# MotorController.net
KiCad netlist of a schematic drawn in Altium Designer
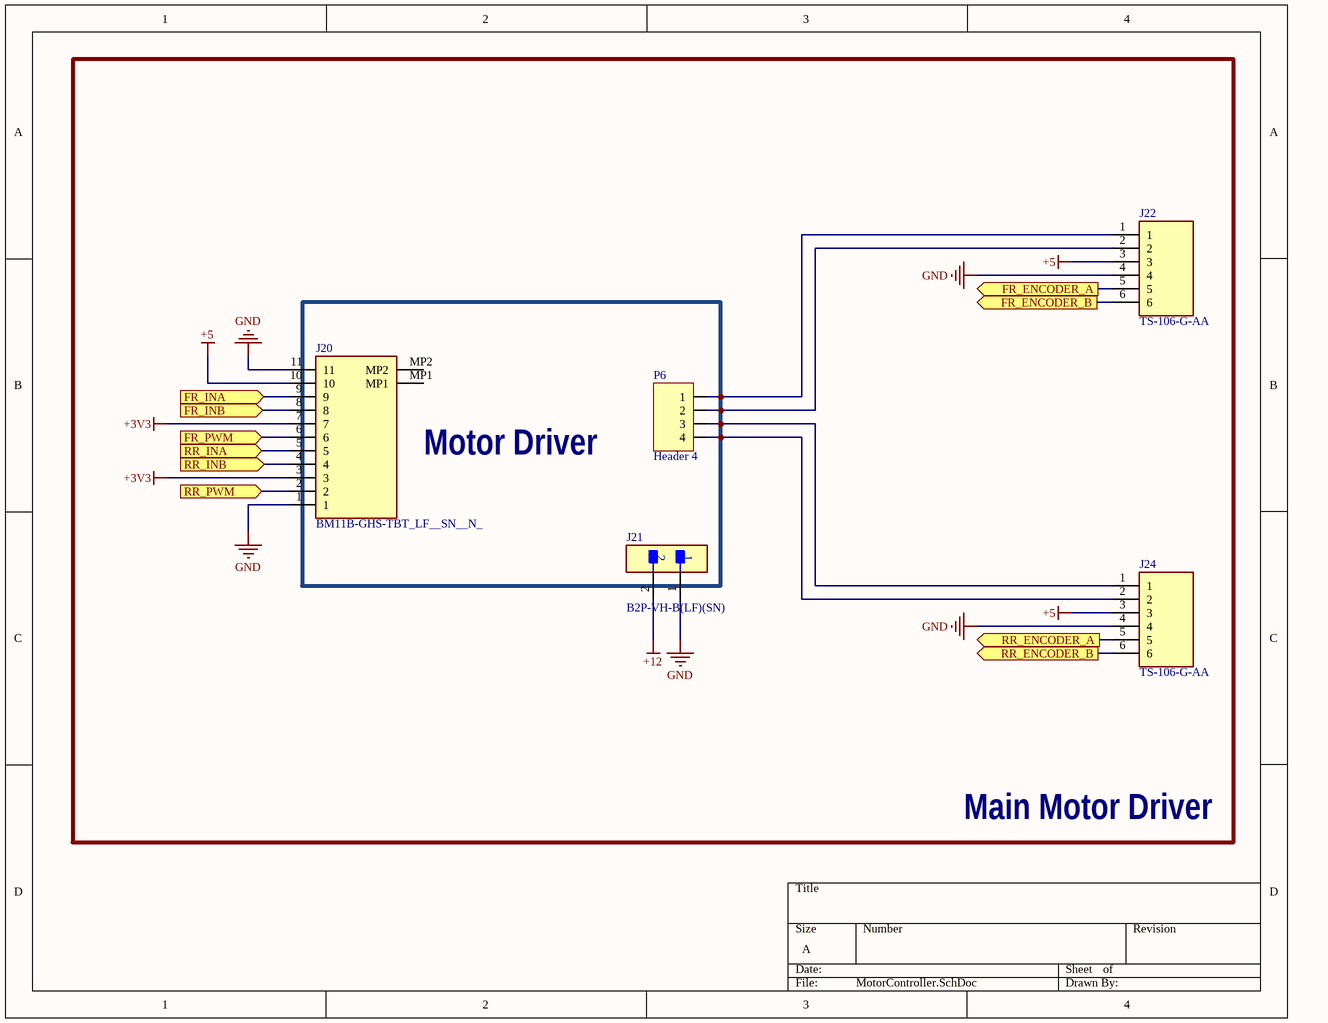
[diagram p0: MotorController.SchDoc]

(export (version "E")
  (design (tool "Eeschema 10.0.6"))
  (components
    (comp (ref "J20")
      (value "BM11B-GHS-TBT_LF__SN__N_")
      (footprint "SamacSys:BM11BGHSTBTLFSNN")
      (description "Connector")
      (fields (field (name "MANUFACTURER_PART_NUMBER") "BM11B-GHS-TBT(LF)(SN)(N)"))
      (libsource (lib "SamacSys") (part "BM11B-GHS-TBT_LF__SN__N_"))
    )
    (comp (ref "J21")
      (value "B2P-VH-B(LF)(SN)")
      (footprint "FP-B2P-VH-B_LF_SN-MFG")
      (description "CONN HEADER VERT 2POS 3.96MM")
      (libsource (lib "Altium Content Vault") (part "3bc925449376181038e59eaffc5286c"))
    )
    (comp (ref "J22")
      (value "TS-106-G-AA")
      (footprint "SamacSys:HDRV6W46P0X254_1X6_1524X254X676P")
      (description "Connector")
      (fields (field (name "MOUSER PART NUMBER") "200-TS106GAA"))
      (libsource (lib "SamacSys") (part "TS-106-G-AA"))
    )
    (comp (ref "J24")
      (value "TS-106-G-AA")
      (footprint "SamacSys:HDRV6W46P0X254_1X6_1524X254X676P")
      (description "Connector")
      (fields (field (name "MOUSER PART NUMBER") "200-TS106GAA"))
      (libsource (lib "SamacSys") (part "TS-106-G-AA"))
    )
    (comp (ref "P6")
      (value "Header 4")
      (footprint "HDR1X4")
      (description "Header, 4-Pin")
      (fields (field (name "PUBLISHER") "Altium Limited"))
      (libsource (lib "Miscellaneous Connectors") (part "Header 4"))
    )
  )
  (nets
    (net (code "1") (name "+3V3") (class "Default")
      (node (ref "J20") (pin "3") (pinfunction "3_3") (pintype "passive"))
      (node (ref "J20") (pin "7") (pinfunction "7_7") (pintype "passive"))
    )
    (net (code "2") (name "+5") (class "Default")
      (node (ref "J20") (pin "10") (pinfunction "10_10") (pintype "passive"))
      (node (ref "J22") (pin "3") (pinfunction "3_3") (pintype "passive"))
      (node (ref "J24") (pin "3") (pinfunction "3_3") (pintype "passive"))
    )
    (net (code "3") (name "+12") (class "Default")
      (node (ref "J21") (pin "2") (pinfunction "2_2") (pintype "passive"))
    )
    (net (code "4") (name "/FR_ENCODER_A") (class "Default")
      (node (ref "J22") (pin "5") (pinfunction "5_5") (pintype "passive"))
    )
    (net (code "5") (name "/FR_ENCODER_B") (class "Default")
      (node (ref "J22") (pin "6") (pinfunction "6_6") (pintype "passive"))
    )
    (net (code "6") (name "/FR_INA") (class "Default")
      (node (ref "J20") (pin "9") (pinfunction "9_9") (pintype "passive"))
    )
    (net (code "7") (name "/FR_INB") (class "Default")
      (node (ref "J20") (pin "8") (pinfunction "8_8") (pintype "passive"))
    )
    (net (code "8") (name "/FR_PWM") (class "Default")
      (node (ref "J20") (pin "6") (pinfunction "6_6") (pintype "passive"))
    )
    (net (code "9") (name "/RR_ENCODER_A") (class "Default")
      (node (ref "J24") (pin "5") (pinfunction "5_5") (pintype "passive"))
    )
    (net (code "10") (name "/RR_ENCODER_B") (class "Default")
      (node (ref "J24") (pin "6") (pinfunction "6_6") (pintype "passive"))
    )
    (net (code "11") (name "/RR_INA") (class "Default")
      (node (ref "J20") (pin "5") (pinfunction "5_5") (pintype "passive"))
    )
    (net (code "12") (name "/RR_INB") (class "Default")
      (node (ref "J20") (pin "4") (pinfunction "4_4") (pintype "passive"))
    )
    (net (code "13") (name "/RR_PWM") (class "Default")
      (node (ref "J20") (pin "2") (pinfunction "2_2") (pintype "passive"))
    )
    (net (code "14") (name "GND") (class "Default")
      (node (ref "J20") (pin "1") (pinfunction "1_1") (pintype "passive"))
      (node (ref "J20") (pin "11") (pinfunction "11_11") (pintype "passive"))
      (node (ref "J21") (pin "1") (pinfunction "1_1") (pintype "passive"))
      (node (ref "J22") (pin "4") (pinfunction "4_4") (pintype "passive"))
      (node (ref "J24") (pin "4") (pinfunction "4_4") (pintype "passive"))
    )
    (net (code "15") (name "Net-(J22-Pad1)") (class "Default")
      (node (ref "J22") (pin "1") (pinfunction "1_1") (pintype "passive"))
      (node (ref "P6") (pin "1") (pinfunction "1_1") (pintype "passive"))
    )
    (net (code "16") (name "Net-(J22-Pad2)") (class "Default")
      (node (ref "J22") (pin "2") (pinfunction "2_2") (pintype "passive"))
      (node (ref "P6") (pin "2") (pinfunction "2_2") (pintype "passive"))
    )
    (net (code "17") (name "Net-(J24-Pad1)") (class "Default")
      (node (ref "J24") (pin "1") (pinfunction "1_1") (pintype "passive"))
      (node (ref "P6") (pin "3") (pinfunction "3_3") (pintype "passive"))
    )
    (net (code "18") (name "Net-(J24-Pad2)") (class "Default")
      (node (ref "J24") (pin "2") (pinfunction "2_2") (pintype "passive"))
      (node (ref "P6") (pin "4") (pinfunction "4_4") (pintype "passive"))
    )
    (net (code "19") (name "unconnected-(J20-PadMP1)") (class "Default")
      (node (ref "J20") (pin "MP1") (pinfunction "MP1_MP1") (pintype "passive"))
    )
    (net (code "20") (name "unconnected-(J20-PadMP2)") (class "Default")
      (node (ref "J20") (pin "MP2") (pinfunction "MP2_MP2") (pintype "passive"))
    )
  )
)
